# Faulhaber_Temp_sensor.net
KiCad netlist of a schematic drawn in EAGLE
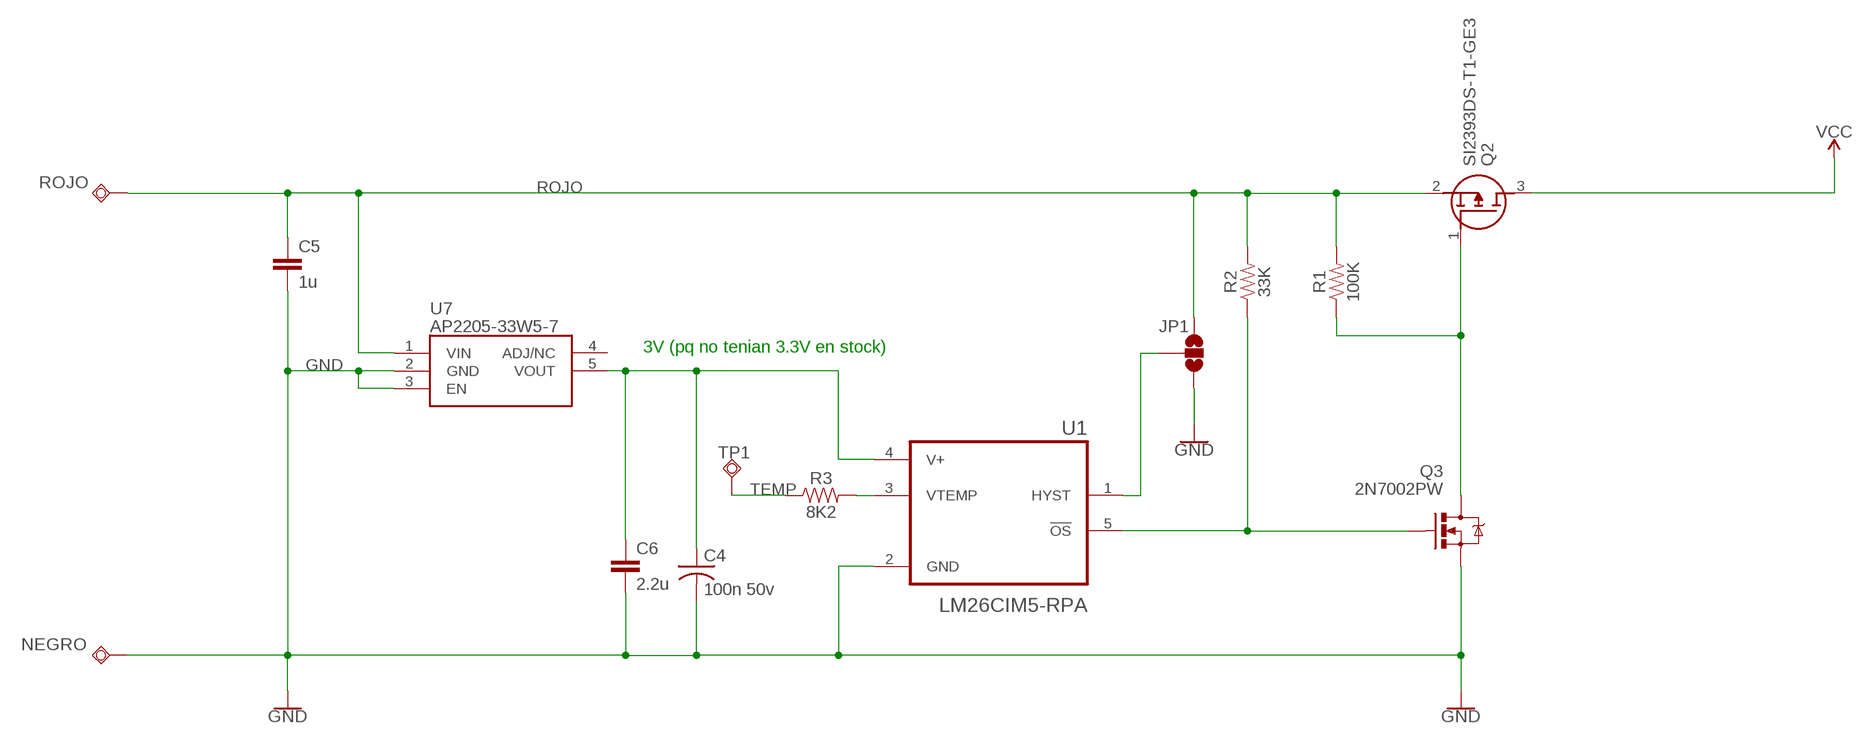
[diagram p0: schematic, sheet 1]

(export (version "E")
  (design (tool "Eeschema 10.0.6"))
  (components
    (comp (ref "C4")
      (value "100n 50v")
      (footprint "eagle-import:C0805")
      (libsource (lib "eagle-import") (part "C-USC0805"))
    )
    (comp (ref "C5")
      (value "1u")
      (footprint "eagle-import:0603-CAP")
      (libsource (lib "eagle-import") (part "4.7UF-6.3V-10%(0603)0603"))
    )
    (comp (ref "C6")
      (value "2.2u")
      (footprint "eagle-import:0603-CAP")
      (libsource (lib "eagle-import") (part "4.7UF-6.3V-10%(0603)0603"))
    )
    (comp (ref "JP1")
      (value "JUMPER-SMT_3_NO_SILK")
      (footprint "eagle-import:SMT-JUMPER_3_NO_SILK")
      (libsource (lib "eagle-import") (part "JUMPER-SMT_3_NO_SILK"))
    )
    (comp (ref "NEGRO")
      (value "TESTPAD_TPSQTP10SQ")
      (footprint "eagle-import:TESTPAD_TP10SQ")
      (libsource (lib "eagle-import") (part "TESTPAD_TPSQTP10SQ"))
    )
    (comp (ref "Q2")
      (value "SI2393DS-T1-GE3")
      (footprint "eagle-import:SOT95P237X112-3N")
      (fields (field (name "MOUSER_PART_NUMBER") "78-SI2393DS-T1-GE3"))
      (libsource (lib "eagle-import") (part "SI2393DS-T1-GE3"))
    )
    (comp (ref "Q3")
      (value "2N7002PW")
      (footprint "eagle-import:SOT323")
      (libsource (lib "eagle-import") (part "MOSFET-NCHANNEL2N7002PW"))
    )
    (comp (ref "R1")
      (value "100K")
      (footprint "eagle-import:0603")
      (libsource (lib "eagle-import") (part "RESISTOR0603"))
    )
    (comp (ref "R2")
      (value "33K")
      (footprint "eagle-import:0603")
      (libsource (lib "eagle-import") (part "RESISTOR0603"))
    )
    (comp (ref "R3")
      (value "8K2")
      (footprint "eagle-import:0603")
      (libsource (lib "eagle-import") (part "RESISTOR0603"))
    )
    (comp (ref "ROJO")
      (value "TESTPAD_TPSQTP10SQ")
      (footprint "eagle-import:TESTPAD_TP10SQ")
      (libsource (lib "eagle-import") (part "TESTPAD_TPSQTP10SQ"))
    )
    (comp (ref "TP1")
      (value "TESTPAD_TPSQTP20R")
      (footprint "eagle-import:TESTPAD_TP20R")
      (libsource (lib "eagle-import") (part "TESTPAD_TPSQTP20R"))
    )
    (comp (ref "U1")
      (value "LM26CIM5-RPA")
      (footprint "eagle-import:SOT95P280X145-5N")
      (libsource (lib "eagle-import") (part "LM26CIM5-RPA"))
    )
    (comp (ref "U7")
      (value "AP2205-33W5-7")
      (footprint "eagle-import:SOT95P282X145-5N")
      (fields
        (field (name "MANUFACTURER_PART_NUMBER") "AP2205-W5-7")
        (field (name "MOUSER_PART_NUMBER") "621-AP2205-W5-7")
      )
      (libsource (lib "eagle-import") (part "AP2205-W5-7"))
    )
  )
  (nets
    (net (code "1") (name "/ROJO") (class "Default")
      (node (ref "C5") (pin "1") (pinfunction "1_1") (pintype "passive"))
      (node (ref "JP1") (pin "1") (pinfunction "1_1") (pintype "passive"))
      (node (ref "Q2") (pin "2") (pinfunction "S_2") (pintype "bidirectional"))
      (node (ref "R1") (pin "2") (pinfunction "2_2") (pintype "passive"))
      (node (ref "R2") (pin "2") (pinfunction "2_2") (pintype "passive"))
      (node (ref "ROJO") (pin "TP") (pinfunction "TP_TP") (pintype "input"))
      (node (ref "U7") (pin "1") (pinfunction "VIN_1") (pintype "bidirectional"))
    )
    (net (code "2") (name "/TEMP") (class "Default")
      (node (ref "R3") (pin "1") (pinfunction "1_1") (pintype "passive"))
      (node (ref "TP1") (pin "TP") (pinfunction "TP_TP") (pintype "input"))
    )
    (net (code "3") (name "GND") (class "Default")
      (node (ref "C4") (pin "2") (pinfunction "2_2") (pintype "passive"))
      (node (ref "C5") (pin "2") (pinfunction "2_2") (pintype "passive"))
      (node (ref "C6") (pin "2") (pinfunction "2_2") (pintype "passive"))
      (node (ref "JP1") (pin "3") (pinfunction "3_3") (pintype "passive"))
      (node (ref "NEGRO") (pin "TP") (pinfunction "TP_TP") (pintype "input"))
      (node (ref "Q3") (pin "2") (pinfunction "S_2") (pintype "passive"))
      (node (ref "U1") (pin "2") (pinfunction "GND_2") (pintype "power_in"))
      (node (ref "U7") (pin "2") (pinfunction "GND_2") (pintype "bidirectional"))
      (node (ref "U7") (pin "3") (pinfunction "EN_3") (pintype "bidirectional"))
    )
    (net (code "4") (name "Net-(Q2-G)") (class "Default")
      (node (ref "Q2") (pin "1") (pinfunction "G_1") (pintype "bidirectional"))
      (node (ref "Q3") (pin "3") (pinfunction "D_3") (pintype "passive"))
      (node (ref "R1") (pin "1") (pinfunction "1_1") (pintype "passive"))
    )
    (net (code "5") (name "Net-(Q3-G)") (class "Default")
      (node (ref "Q3") (pin "1") (pinfunction "G_1") (pintype "passive"))
      (node (ref "R2") (pin "1") (pinfunction "1_1") (pintype "passive"))
      (node (ref "U1") (pin "5") (pinfunction "~{OS}_5") (pintype "bidirectional"))
    )
    (net (code "6") (name "Net-(U1-HYST)") (class "Default")
      (node (ref "JP1") (pin "2") (pinfunction "2_2") (pintype "passive"))
      (node (ref "U1") (pin "1") (pinfunction "HYST_1") (pintype "input"))
    )
    (net (code "7") (name "Net-(U1-V+)") (class "Default")
      (node (ref "C4") (pin "1") (pinfunction "1_1") (pintype "passive"))
      (node (ref "C6") (pin "1") (pinfunction "1_1") (pintype "passive"))
      (node (ref "U1") (pin "4") (pinfunction "V+_4") (pintype "power_in"))
      (node (ref "U7") (pin "5") (pinfunction "VOUT_5") (pintype "bidirectional"))
    )
    (net (code "8") (name "Net-(U1-VTEMP)") (class "Default")
      (node (ref "R3") (pin "2") (pinfunction "2_2") (pintype "passive"))
      (node (ref "U1") (pin "3") (pinfunction "VTEMP_3") (pintype "output"))
    )
    (net (code "9") (name "VCC") (class "Default")
      (node (ref "Q2") (pin "3") (pinfunction "D_3") (pintype "bidirectional"))
    )
    (net (code "10") (name "unconnected-(U7-ADJ{slash}NC-Pad4)") (class "Default")
      (node (ref "U7") (pin "4") (pinfunction "ADJ/NC_4") (pintype "bidirectional"))
    )
  )
)
